# ExtPlateSheet1.net
KiCad netlist of a schematic drawn in Altium Designer
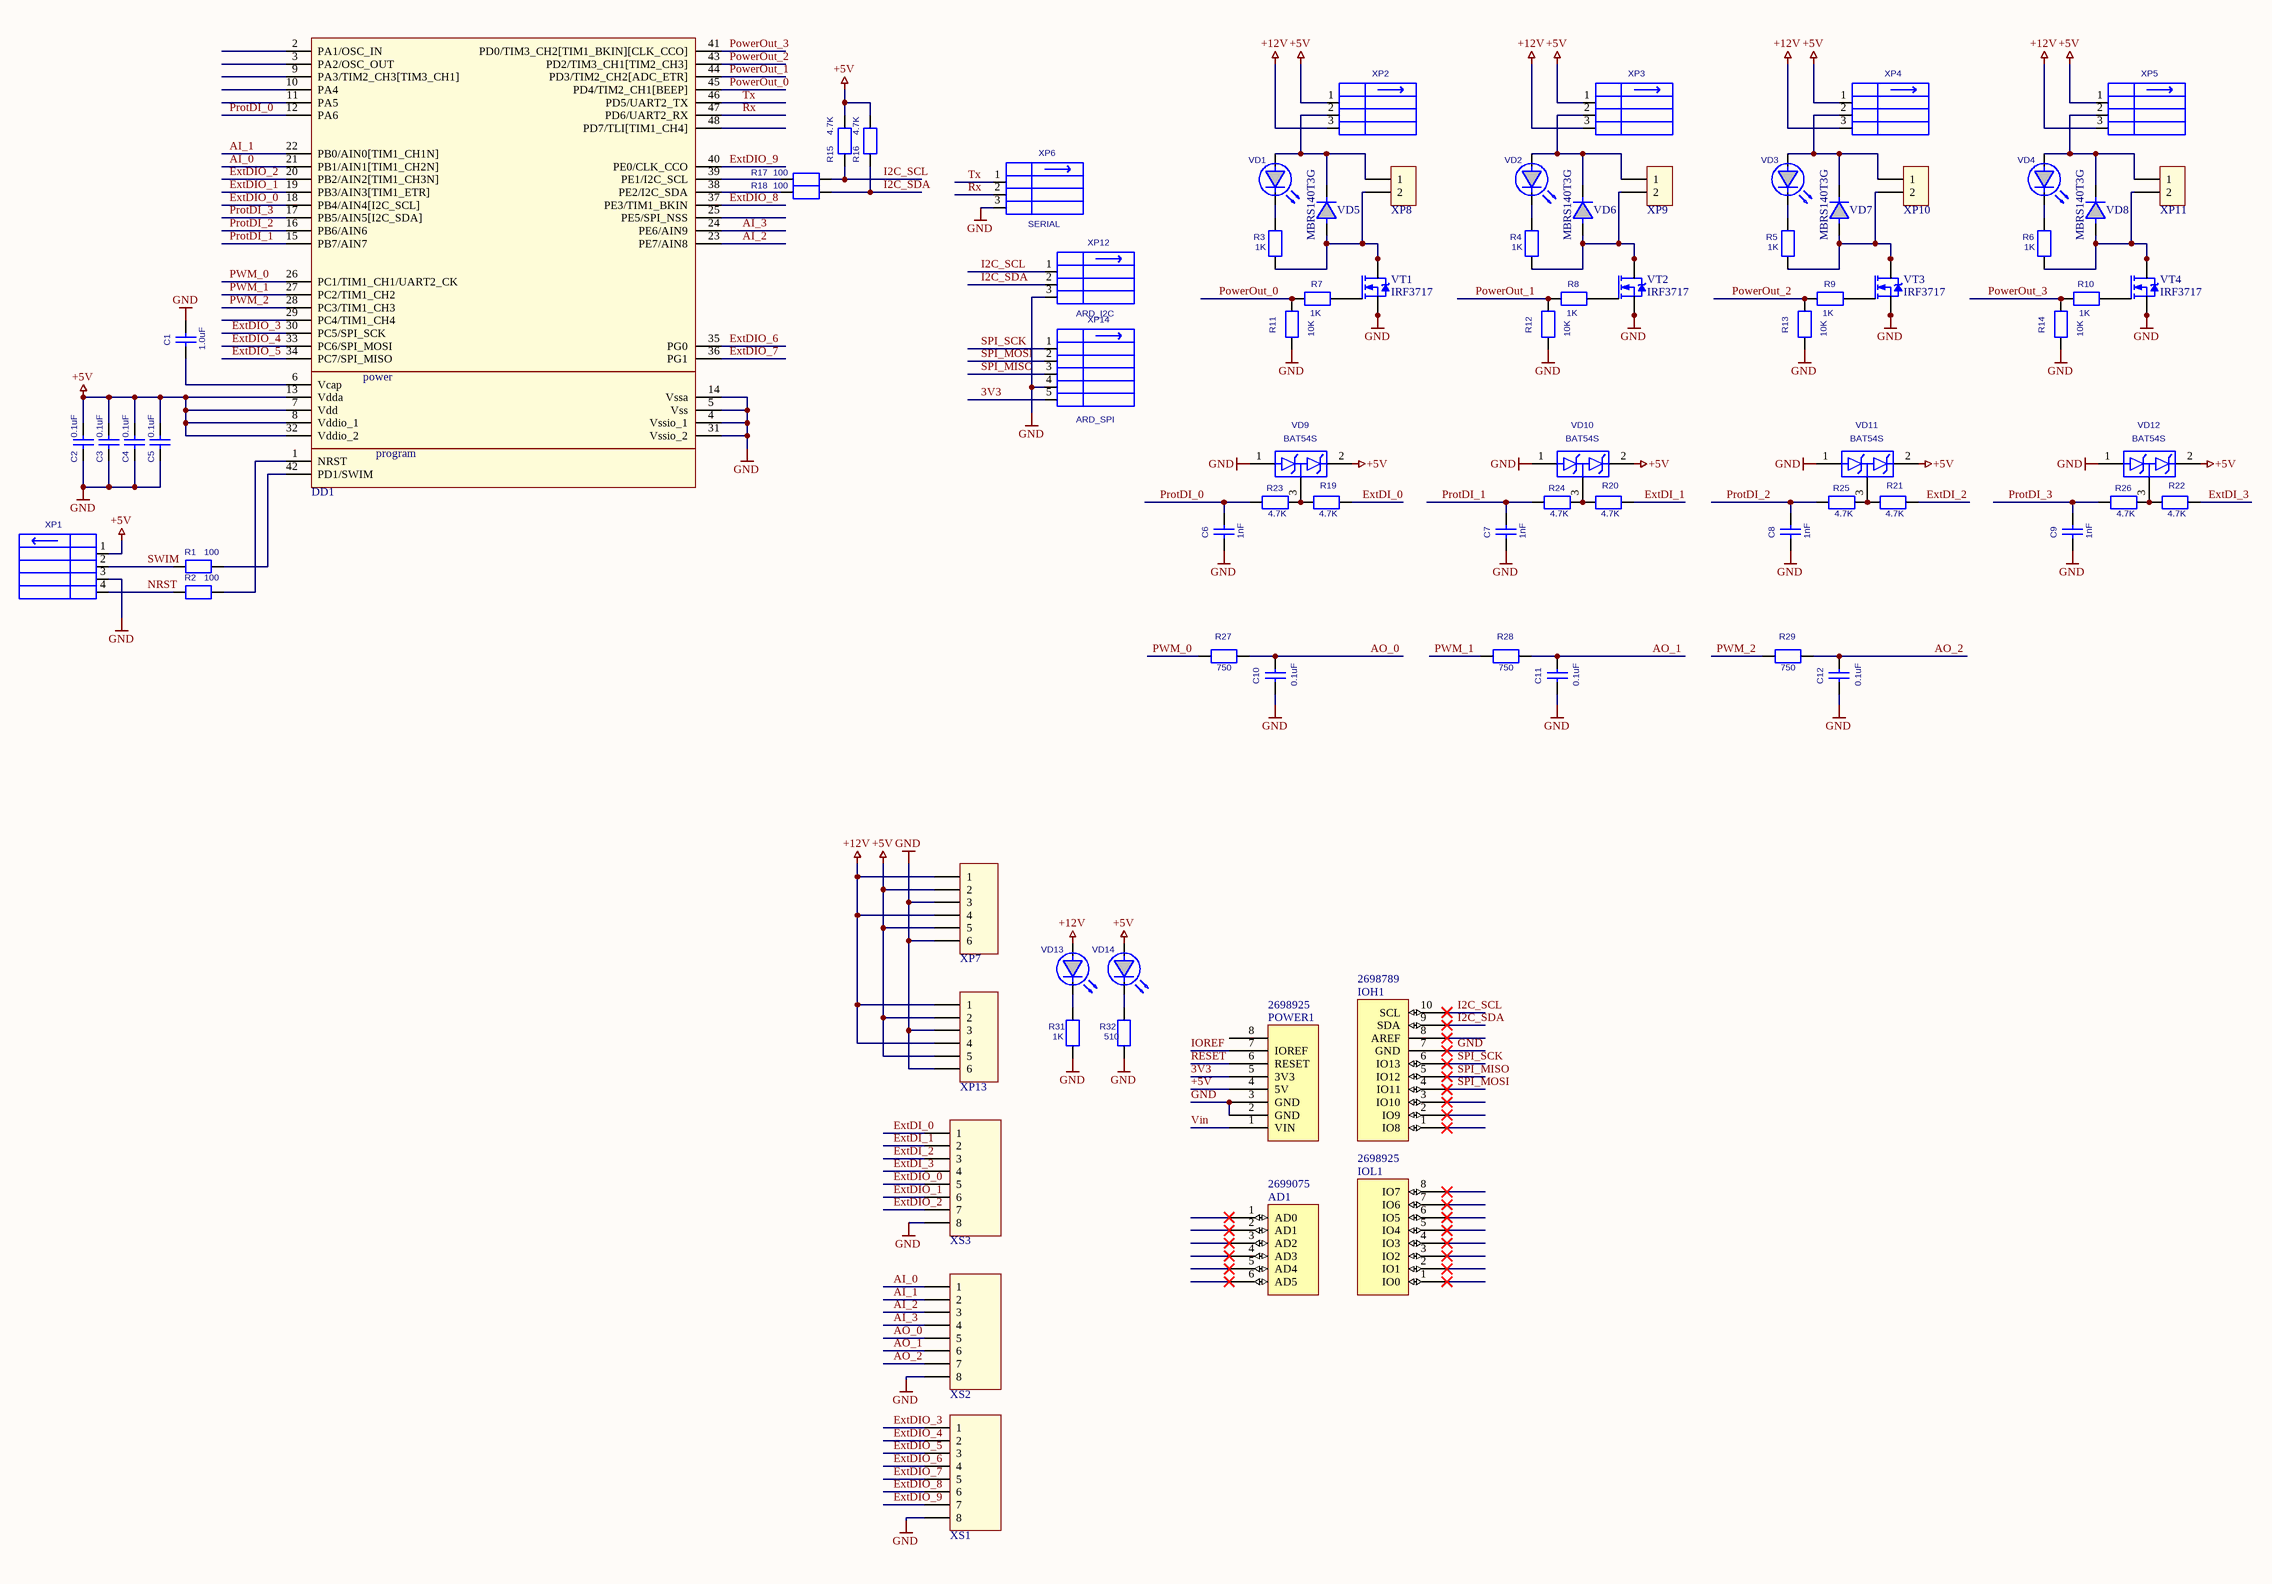
[diagram p0: ExtPlateSheet1.SchDoc]

(export (version "E")
  (design (tool "Eeschema 10.0.6"))
  (components
    (comp (ref "AD1")
      (value "AD")
      (footprint "Altium-CONN:PLS6")
      (fields (field (name "SUPPLIER PART NUMBER 4") "2699075"))
      (libsource (lib "Header") (part "AD"))
    )
    (comp (ref "C1")
      (value "1.0uF")
      (footprint "C-1608[0603]")
      (description "C-0603")
      (libsource (lib "Altium-RC") (part "C-0603"))
    )
    (comp (ref "C2")
      (value "0.1uF")
      (footprint "C-1608[0603]")
      (description "C-0603")
      (libsource (lib "Altium-RC") (part "C-0603"))
    )
    (comp (ref "C3")
      (value "0.1uF")
      (footprint "C-1608[0603]")
      (description "C-0603")
      (libsource (lib "Altium-RC") (part "C-0603"))
    )
    (comp (ref "C4")
      (value "0.1uF")
      (footprint "C-1608[0603]")
      (description "C-0603")
      (libsource (lib "Altium-RC") (part "C-0603"))
    )
    (comp (ref "C5")
      (value "0.1uF")
      (footprint "C-1608[0603]")
      (description "C-0603")
      (libsource (lib "Altium-RC") (part "C-0603"))
    )
    (comp (ref "C6")
      (value "1nF")
      (footprint "C-1608[0603]")
      (description "C-0603")
      (libsource (lib "Altium-RC") (part "C-0603"))
    )
    (comp (ref "C7")
      (value "1nF")
      (footprint "C-1608[0603]")
      (description "C-0603")
      (libsource (lib "Altium-RC") (part "C-0603"))
    )
    (comp (ref "C8")
      (value "1nF")
      (footprint "C-1608[0603]")
      (description "C-0603")
      (libsource (lib "Altium-RC") (part "C-0603"))
    )
    (comp (ref "C9")
      (value "1nF")
      (footprint "C-1608[0603]")
      (description "C-0603")
      (libsource (lib "Altium-RC") (part "C-0603"))
    )
    (comp (ref "C10")
      (value "0.1uF")
      (footprint "C-1608[0603]")
      (description "C-0603")
      (libsource (lib "Altium-RC") (part "C-0603"))
    )
    (comp (ref "C11")
      (value "0.1uF")
      (footprint "C-1608[0603]")
      (description "C-0603")
      (libsource (lib "Altium-RC") (part "C-0603"))
    )
    (comp (ref "C12")
      (value "0.1uF")
      (footprint "C-1608[0603]")
      (description "C-0603")
      (libsource (lib "Altium-RC") (part "C-0603"))
    )
    (comp (ref "DD1")
      (value "STM8S105Cx")
      (footprint "LQFP48_N")
      (description "Access line, 16 MHz STM8S 8-bit MCU")
      (libsource (lib "Schlib1") (part "STM8S105C"))
    )
    (comp (ref "IOH1")
      (value "IOH")
      (footprint "Altium-CONN:PLS10")
      (fields (field (name "SUPPLIER PART NUMBER 3") "2698789"))
      (libsource (lib "Header") (part "IOH"))
    )
    (comp (ref "IOL1")
      (value "IOL")
      (footprint "PLS8")
      (fields (field (name "SUPPLIER PART NUMBER 4") "2698925"))
      (libsource (lib "Header") (part "IOL"))
    )
    (comp (ref "POWER1")
      (value "POWER_UNO")
      (footprint "PLS8")
      (fields (field (name "SUPPLIER PART NUMBER 4") "2698925"))
      (libsource (lib "Header") (part "POWER_UNO"))
    )
    (comp (ref "R1")
      (value "100")
      (footprint "R-1608[0603]")
      (description "R-0603")
      (libsource (lib "Altium-RC") (part "R-0603"))
    )
    (comp (ref "R2")
      (value "100")
      (footprint "R-1608[0603]")
      (description "R-0603")
      (libsource (lib "Altium-RC") (part "R-0603"))
    )
    (comp (ref "R3")
      (value "1K")
      (footprint "R-1608[0603]")
      (description "R-0603")
      (libsource (lib "Altium-RC") (part "R-0603"))
    )
    (comp (ref "R4")
      (value "1K")
      (footprint "R-1608[0603]")
      (description "R-0603")
      (libsource (lib "Altium-RC") (part "R-0603"))
    )
    (comp (ref "R5")
      (value "1K")
      (footprint "R-1608[0603]")
      (description "R-0603")
      (libsource (lib "Altium-RC") (part "R-0603"))
    )
    (comp (ref "R6")
      (value "1K")
      (footprint "R-1608[0603]")
      (description "R-0603")
      (libsource (lib "Altium-RC") (part "R-0603"))
    )
    (comp (ref "R7")
      (value "1K")
      (footprint "R-1608[0603]")
      (description "R-0603")
      (libsource (lib "Altium-RC") (part "R-0603"))
    )
    (comp (ref "R8")
      (value "1K")
      (footprint "R-1608[0603]")
      (description "R-0603")
      (libsource (lib "Altium-RC") (part "R-0603"))
    )
    (comp (ref "R9")
      (value "1K")
      (footprint "R-1608[0603]")
      (description "R-0603")
      (libsource (lib "Altium-RC") (part "R-0603"))
    )
    (comp (ref "R10")
      (value "1K")
      (footprint "R-1608[0603]")
      (description "R-0603")
      (libsource (lib "Altium-RC") (part "R-0603"))
    )
    (comp (ref "R11")
      (value "10K")
      (footprint "R-1608[0603]")
      (description "R-0603")
      (libsource (lib "Altium-RC") (part "R-0603"))
    )
    (comp (ref "R12")
      (value "10K")
      (footprint "R-1608[0603]")
      (description "R-0603")
      (libsource (lib "Altium-RC") (part "R-0603"))
    )
    (comp (ref "R13")
      (value "10K")
      (footprint "R-1608[0603]")
      (description "R-0603")
      (libsource (lib "Altium-RC") (part "R-0603"))
    )
    (comp (ref "R14")
      (value "10K")
      (footprint "R-1608[0603]")
      (description "R-0603")
      (libsource (lib "Altium-RC") (part "R-0603"))
    )
    (comp (ref "R15")
      (value "4.7K")
      (footprint "R-1608[0603]")
      (description "R-0603")
      (libsource (lib "Altium-RC") (part "R-0603"))
    )
    (comp (ref "R16")
      (value "4.7K")
      (footprint "R-1608[0603]")
      (description "R-0603")
      (libsource (lib "Altium-RC") (part "R-0603"))
    )
    (comp (ref "R17")
      (value "100")
      (footprint "R-1608[0603]")
      (description "R-0603")
      (libsource (lib "Altium-RC") (part "R-0603"))
    )
    (comp (ref "R18")
      (value "100")
      (footprint "R-1608[0603]")
      (description "R-0603")
      (libsource (lib "Altium-RC") (part "R-0603"))
    )
    (comp (ref "R19")
      (value "4.7K")
      (footprint "R-1608[0603]")
      (description "R-0603")
      (libsource (lib "Altium-RC") (part "R-0603"))
    )
    (comp (ref "R20")
      (value "4.7K")
      (footprint "R-1608[0603]")
      (description "R-0603")
      (libsource (lib "Altium-RC") (part "R-0603"))
    )
    (comp (ref "R21")
      (value "4.7K")
      (footprint "R-1608[0603]")
      (description "R-0603")
      (libsource (lib "Altium-RC") (part "R-0603"))
    )
    (comp (ref "R22")
      (value "4.7K")
      (footprint "R-1608[0603]")
      (description "R-0603")
      (libsource (lib "Altium-RC") (part "R-0603"))
    )
    (comp (ref "R23")
      (value "4.7K")
      (footprint "R-1608[0603]")
      (description "R-0603")
      (libsource (lib "Altium-RC") (part "R-0603"))
    )
    (comp (ref "R24")
      (value "4.7K")
      (footprint "R-1608[0603]")
      (description "R-0603")
      (libsource (lib "Altium-RC") (part "R-0603"))
    )
    (comp (ref "R25")
      (value "4.7K")
      (footprint "R-1608[0603]")
      (description "R-0603")
      (libsource (lib "Altium-RC") (part "R-0603"))
    )
    (comp (ref "R26")
      (value "4.7K")
      (footprint "R-1608[0603]")
      (description "R-0603")
      (libsource (lib "Altium-RC") (part "R-0603"))
    )
    (comp (ref "R27")
      (value "750")
      (footprint "R-1608[0603]")
      (description "R-0603")
      (libsource (lib "Altium-RC") (part "R-0603"))
    )
    (comp (ref "R28")
      (value "750")
      (footprint "R-1608[0603]")
      (description "R-0603")
      (libsource (lib "Altium-RC") (part "R-0603"))
    )
    (comp (ref "R29")
      (value "750")
      (footprint "R-1608[0603]")
      (description "R-0603")
      (libsource (lib "Altium-RC") (part "R-0603"))
    )
    (comp (ref "R31")
      (value "1K")
      (footprint "R-1608[0603]")
      (description "R-0603")
      (libsource (lib "Altium-RC") (part "R-0603"))
    )
    (comp (ref "R32")
      (value "510")
      (footprint "R-1608[0603]")
      (description "R-0603")
      (libsource (lib "Altium-RC") (part "R-0603"))
    )
    (comp (ref "VD1")
      (value "KB170G")
      (footprint "LED-2012[0805]")
      (description "Green Led 0805")
      (libsource (lib "Altium-OPTO") (part "KB170G"))
    )
    (comp (ref "VD2")
      (value "KB170G")
      (footprint "LED-2012[0805]")
      (description "Green Led 0805")
      (libsource (lib "Altium-OPTO") (part "KB170G"))
    )
    (comp (ref "VD3")
      (value "KB170G")
      (footprint "LED-2012[0805]")
      (description "Green Led 0805")
      (libsource (lib "Altium-OPTO") (part "KB170G"))
    )
    (comp (ref "VD4")
      (value "KB170G")
      (footprint "LED-2012[0805]")
      (description "Green Led 0805")
      (libsource (lib "Altium-OPTO") (part "KB170G"))
    )
    (comp (ref "VD5")
      (value "MBRS140T3G")
      (footprint "SMB")
      (description "Surface Mount Schottky Power Rectifier")
      (libsource (lib "Altium-RECT") (part "MBRS140T3G"))
    )
    (comp (ref "VD6")
      (value "MBRS140T3G")
      (footprint "SMB")
      (description "Surface Mount Schottky Power Rectifier")
      (libsource (lib "Altium-RECT") (part "MBRS140T3G"))
    )
    (comp (ref "VD7")
      (value "MBRS140T3G")
      (footprint "SMB")
      (description "Surface Mount Schottky Power Rectifier")
      (libsource (lib "Altium-RECT") (part "MBRS140T3G"))
    )
    (comp (ref "VD8")
      (value "MBRS140T3G")
      (footprint "SMB")
      (description "Surface Mount Schottky Power Rectifier")
      (libsource (lib "Altium-RECT") (part "MBRS140T3G"))
    )
    (comp (ref "VD9")
      (value "BAT54S")
      (footprint "SOT-23")
      (description "Schottky barrier (double) diodes")
      (libsource (lib "Altium-RECT") (part "BAT54S"))
    )
    (comp (ref "VD10")
      (value "BAT54S")
      (footprint "SOT-23")
      (description "Schottky barrier (double) diodes")
      (libsource (lib "Altium-RECT") (part "BAT54S"))
    )
    (comp (ref "VD11")
      (value "BAT54S")
      (footprint "SOT-23")
      (description "Schottky barrier (double) diodes")
      (libsource (lib "Altium-RECT") (part "BAT54S"))
    )
    (comp (ref "VD12")
      (value "BAT54S")
      (footprint "SOT-23")
      (description "Schottky barrier (double) diodes")
      (libsource (lib "Altium-RECT") (part "BAT54S"))
    )
    (comp (ref "VD13")
      (value "KB170G")
      (footprint "LED-2012[0805]")
      (description "Green Led 0805")
      (libsource (lib "Altium-OPTO") (part "KB170G"))
    )
    (comp (ref "VD14")
      (value "KB170G")
      (footprint "LED-2012[0805]")
      (description "Green Led 0805")
      (libsource (lib "Altium-OPTO") (part "KB170G"))
    )
    (comp (ref "VT1") (value "IRF3717") (footprint "SO8") (libsource (lib "Altium-RECT") (part "IRF3717")))
    (comp (ref "VT2") (value "IRF3717") (footprint "SO8") (libsource (lib "Altium-RECT") (part "IRF3717")))
    (comp (ref "VT3") (value "IRF3717") (footprint "SO8") (libsource (lib "Altium-RECT") (part "IRF3717")))
    (comp (ref "VT4") (value "IRF3717") (footprint "SO8") (libsource (lib "Altium-RECT") (part "IRF3717")))
    (comp (ref "XP1") (value "PLS-4") (footprint "PLS4") (libsource (lib "Altium-CONN") (part "PLS-4")))
    (comp (ref "XP2") (value "PLS-3") (footprint "PLS3") (libsource (lib "Altium-CONN") (part "PLS-3")))
    (comp (ref "XP3") (value "PLS-3") (footprint "PLS3") (libsource (lib "Altium-CONN") (part "PLS-3")))
    (comp (ref "XP4") (value "PLS-3") (footprint "PLS3") (libsource (lib "Altium-CONN") (part "PLS-3")))
    (comp (ref "XP5") (value "PLS-3") (footprint "PLS3") (libsource (lib "Altium-CONN") (part "PLS-3")))
    (comp (ref "XP6")
      (value "SERIAL")
      (footprint "PLS3")
      (description "PLS-3")
      (libsource (lib "Altium-CONN") (part "PLS-3"))
    )
    (comp (ref "XP7")
      (value "MF-6M")
      (footprint "MF-6M")
      (description "Mini-Fit 6 pin Connector on board.")
      (libsource (lib "Schlib1") (part "MF-6M"))
    )
    (comp (ref "XP8")
      (value "2EDGR-5.08")
      (footprint "2EDGR-5.08")
      (libsource (lib "Schlib1") (part "2EDGR-5.08"))
    )
    (comp (ref "XP9")
      (value "2EDGR-5.08")
      (footprint "2EDGR-5.08")
      (libsource (lib "Schlib1") (part "2EDGR-5.08"))
    )
    (comp (ref "XP10")
      (value "2EDGR-5.08")
      (footprint "2EDGR-5.08")
      (libsource (lib "Schlib1") (part "2EDGR-5.08"))
    )
    (comp (ref "XP11")
      (value "2EDGR-5.08")
      (footprint "2EDGR-5.08")
      (libsource (lib "Schlib1") (part "2EDGR-5.08"))
    )
    (comp (ref "XP12")
      (value "ARD_I2C")
      (footprint "PLS3")
      (description "PLS-3")
      (libsource (lib "Altium-CONN") (part "PLS-3"))
    )
    (comp (ref "XP13")
      (value "MF-6M")
      (footprint "MF-6M")
      (description "Mini-Fit 6 pin Connector on board.")
      (libsource (lib "Schlib1") (part "MF-6M"))
    )
    (comp (ref "XP14")
      (value "ARD_SPI")
      (footprint "PLS5")
      (description "PLS-5")
      (libsource (lib "Altium-CONN") (part "PLS-5"))
    )
    (comp (ref "XS1")
      (value "5555164-1")
      (footprint "RJ45 8pin")
      (description "PCB Mounted Jacks - Single Port, Multi-port and Stacked")
      (libsource (lib "Schlib1") (part "5555164-1"))
    )
    (comp (ref "XS2")
      (value "5555164-1")
      (footprint "RJ45 8pin")
      (description "PCB Mounted Jacks - Single Port, Multi-port and Stacked")
      (libsource (lib "Schlib1") (part "5555164-1"))
    )
    (comp (ref "XS3")
      (value "5555164-1")
      (footprint "RJ45 8pin")
      (description "PCB Mounted Jacks - Single Port, Multi-port and Stacked")
      (libsource (lib "Schlib1") (part "5555164-1"))
    )
  )
  (nets
    (net (code "1") (name "+5V") (class "Default")
      (node (ref "C2") (pin "1") (pintype "passive"))
      (node (ref "C3") (pin "1") (pintype "passive"))
      (node (ref "C4") (pin "1") (pintype "passive"))
      (node (ref "C5") (pin "1") (pintype "passive"))
      (node (ref "DD1") (pin "13") (pinfunction "Vdda_13") (pintype "passive"))
      (node (ref "DD1") (pin "32") (pinfunction "Vddio_2_32") (pintype "passive"))
      (node (ref "DD1") (pin "7") (pinfunction "Vdd_7") (pintype "passive"))
      (node (ref "DD1") (pin "8") (pinfunction "Vddio_1_8") (pintype "passive"))
      (node (ref "POWER1") (pin "4") (pinfunction "5V_4") (pintype "power_in"))
      (node (ref "R15") (pin "2") (pinfunction "2_2") (pintype "passive"))
      (node (ref "R16") (pin "2") (pinfunction "2_2") (pintype "passive"))
      (node (ref "VD10") (pin "2") (pinfunction "c_2") (pintype "passive"))
      (node (ref "VD11") (pin "2") (pinfunction "c_2") (pintype "passive"))
      (node (ref "VD12") (pin "2") (pinfunction "c_2") (pintype "passive"))
      (node (ref "VD14") (pin "2") (pinfunction "A_2") (pintype "passive"))
      (node (ref "VD9") (pin "2") (pinfunction "c_2") (pintype "passive"))
      (node (ref "XP1") (pin "1") (pintype "passive"))
      (node (ref "XP13") (pin "2") (pinfunction "2_2") (pintype "passive"))
      (node (ref "XP13") (pin "5") (pinfunction "5_5") (pintype "passive"))
      (node (ref "XP2") (pin "1") (pintype "passive"))
      (node (ref "XP3") (pin "1") (pintype "passive"))
      (node (ref "XP4") (pin "1") (pintype "passive"))
      (node (ref "XP5") (pin "1") (pintype "passive"))
      (node (ref "XP7") (pin "2") (pinfunction "2_2") (pintype "passive"))
      (node (ref "XP7") (pin "5") (pinfunction "5_5") (pintype "passive"))
    )
    (net (code "2") (name "+12V") (class "Default")
      (node (ref "VD13") (pin "2") (pinfunction "A_2") (pintype "passive"))
      (node (ref "XP13") (pin "1") (pinfunction "1_1") (pintype "passive"))
      (node (ref "XP13") (pin "4") (pinfunction "4_4") (pintype "passive"))
      (node (ref "XP2") (pin "3") (pintype "passive"))
      (node (ref "XP3") (pin "3") (pintype "passive"))
      (node (ref "XP4") (pin "3") (pintype "passive"))
      (node (ref "XP5") (pin "3") (pintype "passive"))
      (node (ref "XP7") (pin "1") (pinfunction "1_1") (pintype "passive"))
      (node (ref "XP7") (pin "4") (pinfunction "4_4") (pintype "passive"))
    )
    (net (code "3") (name "/3V3") (class "Default")
      (node (ref "POWER1") (pin "5") (pinfunction "3V3_5") (pintype "power_in"))
      (node (ref "XP14") (pin "5") (pintype "passive"))
    )
    (net (code "5") (name "/AI_0") (class "Default")
      (node (ref "DD1") (pin "21") (pinfunction "PB1/AIN1[TIM1_CH2N]_21") (pintype "passive"))
      (node (ref "XS2") (pin "1") (pinfunction "1_1") (pintype "passive"))
    )
    (net (code "6") (name "/AI_1") (class "Default")
      (node (ref "DD1") (pin "22") (pinfunction "PB0/AIN0[TIM1_CH1N]_22") (pintype "passive"))
      (node (ref "XS2") (pin "2") (pinfunction "2_2") (pintype "passive"))
    )
    (net (code "7") (name "/AI_2") (class "Default")
      (node (ref "DD1") (pin "23") (pinfunction "PE7/AIN8_23") (pintype "passive"))
      (node (ref "XS2") (pin "3") (pinfunction "3_3") (pintype "passive"))
    )
    (net (code "8") (name "/AI_3") (class "Default")
      (node (ref "DD1") (pin "24") (pinfunction "PE6/AIN9_24") (pintype "passive"))
      (node (ref "XS2") (pin "4") (pinfunction "4_4") (pintype "passive"))
    )
    (net (code "9") (name "/AO_0") (class "Default")
      (node (ref "C10") (pin "1") (pintype "passive"))
      (node (ref "R27") (pin "2") (pinfunction "2_2") (pintype "passive"))
      (node (ref "XS2") (pin "5") (pinfunction "5_5") (pintype "passive"))
    )
    (net (code "10") (name "/AO_1") (class "Default")
      (node (ref "C11") (pin "1") (pintype "passive"))
      (node (ref "R28") (pin "2") (pinfunction "2_2") (pintype "passive"))
      (node (ref "XS2") (pin "6") (pinfunction "6_6") (pintype "passive"))
    )
    (net (code "11") (name "/AO_2") (class "Default")
      (node (ref "C12") (pin "1") (pintype "passive"))
      (node (ref "R29") (pin "2") (pinfunction "2_2") (pintype "passive"))
      (node (ref "XS2") (pin "7") (pinfunction "7_7") (pintype "passive"))
    )
    (net (code "12") (name "/ExtDIO_0") (class "Default")
      (node (ref "DD1") (pin "18") (pinfunction "PB4/AIN4[I2C_SCL]_18") (pintype "passive"))
      (node (ref "XS3") (pin "5") (pinfunction "5_5") (pintype "passive"))
    )
    (net (code "13") (name "/ExtDIO_1") (class "Default")
      (node (ref "DD1") (pin "19") (pinfunction "PB3/AIN3[TIM1_ETR]_19") (pintype "passive"))
      (node (ref "XS3") (pin "6") (pinfunction "6_6") (pintype "passive"))
    )
    (net (code "14") (name "/ExtDIO_2") (class "Default")
      (node (ref "DD1") (pin "20") (pinfunction "PB2/AIN2[TIM1_CH3N]_20") (pintype "passive"))
      (node (ref "XS3") (pin "7") (pinfunction "7_7") (pintype "passive"))
    )
    (net (code "15") (name "/ExtDIO_3") (class "Default")
      (node (ref "DD1") (pin "30") (pinfunction "PC5/SPI_SCK_30") (pintype "passive"))
      (node (ref "XS1") (pin "1") (pinfunction "1_1") (pintype "passive"))
    )
    (net (code "16") (name "/ExtDIO_4") (class "Default")
      (node (ref "DD1") (pin "33") (pinfunction "PC6/SPI_MOSI_33") (pintype "passive"))
      (node (ref "XS1") (pin "2") (pinfunction "2_2") (pintype "passive"))
    )
    (net (code "17") (name "/ExtDIO_5") (class "Default")
      (node (ref "DD1") (pin "34") (pinfunction "PC7/SPI_MISO_34") (pintype "passive"))
      (node (ref "XS1") (pin "3") (pinfunction "3_3") (pintype "passive"))
    )
    (net (code "18") (name "/ExtDIO_6") (class "Default")
      (node (ref "DD1") (pin "35") (pinfunction "PG0_35") (pintype "passive"))
      (node (ref "XS1") (pin "4") (pinfunction "4_4") (pintype "passive"))
    )
    (net (code "19") (name "/ExtDIO_7") (class "Default")
      (node (ref "DD1") (pin "36") (pinfunction "PG1_36") (pintype "passive"))
      (node (ref "XS1") (pin "5") (pinfunction "5_5") (pintype "passive"))
    )
    (net (code "20") (name "/ExtDIO_8") (class "Default")
      (node (ref "DD1") (pin "37") (pinfunction "PE3/TIM1_BKIN_37") (pintype "passive"))
      (node (ref "XS1") (pin "6") (pinfunction "6_6") (pintype "passive"))
    )
    (net (code "21") (name "/ExtDIO_9") (class "Default")
      (node (ref "DD1") (pin "40") (pinfunction "PE0/CLK_CCO_40") (pintype "passive"))
      (node (ref "XS1") (pin "7") (pinfunction "7_7") (pintype "passive"))
    )
    (net (code "22") (name "/ExtDI_0") (class "Default")
      (node (ref "R19") (pin "2") (pinfunction "2_2") (pintype "passive"))
      (node (ref "XS3") (pin "1") (pinfunction "1_1") (pintype "passive"))
    )
    (net (code "23") (name "/ExtDI_1") (class "Default")
      (node (ref "R20") (pin "2") (pinfunction "2_2") (pintype "passive"))
      (node (ref "XS3") (pin "2") (pinfunction "2_2") (pintype "passive"))
    )
    (net (code "24") (name "/ExtDI_2") (class "Default")
      (node (ref "R21") (pin "2") (pinfunction "2_2") (pintype "passive"))
      (node (ref "XS3") (pin "3") (pinfunction "3_3") (pintype "passive"))
    )
    (net (code "25") (name "/ExtDI_3") (class "Default")
      (node (ref "R22") (pin "2") (pinfunction "2_2") (pintype "passive"))
      (node (ref "XS3") (pin "4") (pinfunction "4_4") (pintype "passive"))
    )
    (net (code "26") (name "/I2C_SCL") (class "Default")
      (node (ref "IOH1") (pin "10") (pinfunction "SCL_10") (pintype "bidirectional"))
      (node (ref "R15") (pin "1") (pinfunction "1_1") (pintype "passive"))
      (node (ref "R17") (pin "2") (pinfunction "2_2") (pintype "passive"))
      (node (ref "XP12") (pin "1") (pintype "passive"))
    )
    (net (code "27") (name "/I2C_SDA") (class "Default")
      (node (ref "IOH1") (pin "9") (pinfunction "SDA_9") (pintype "bidirectional"))
      (node (ref "R16") (pin "1") (pinfunction "1_1") (pintype "passive"))
      (node (ref "R18") (pin "2") (pinfunction "2_2") (pintype "passive"))
      (node (ref "XP12") (pin "2") (pintype "passive"))
    )
    (net (code "28") (name "/IOREF") (class "Default")
      (node (ref "POWER1") (pin "7") (pinfunction "IOREF_7") (pintype "power_in"))
    )
    (net (code "29") (name "/NRST") (class "Default")
      (node (ref "R2") (pin "1") (pinfunction "1_1") (pintype "passive"))
      (node (ref "XP1") (pin "4") (pintype "passive"))
    )
    (net (code "30") (name "/PWM_0") (class "Default")
      (node (ref "DD1") (pin "26") (pinfunction "PC1/TIM1_CH1/UART2_CK_26") (pintype "passive"))
      (node (ref "R27") (pin "1") (pinfunction "1_1") (pintype "passive"))
    )
    (net (code "31") (name "/PWM_1") (class "Default")
      (node (ref "DD1") (pin "27") (pinfunction "PC2/TIM1_CH2_27") (pintype "passive"))
      (node (ref "R28") (pin "1") (pinfunction "1_1") (pintype "passive"))
    )
    (net (code "32") (name "/PWM_2") (class "Default")
      (node (ref "DD1") (pin "28") (pinfunction "PC3/TIM1_CH3_28") (pintype "passive"))
      (node (ref "R29") (pin "1") (pinfunction "1_1") (pintype "passive"))
    )
    (net (code "33") (name "/PowerOut_0") (class "Default")
      (node (ref "DD1") (pin "45") (pinfunction "PD4/TIM2_CH1[BEEP]_45") (pintype "passive"))
      (node (ref "R11") (pin "2") (pinfunction "2_2") (pintype "passive"))
      (node (ref "R7") (pin "2") (pinfunction "2_2") (pintype "passive"))
    )
    (net (code "34") (name "/PowerOut_1") (class "Default")
      (node (ref "DD1") (pin "44") (pinfunction "PD3/TIM2_CH2[ADC_ETR]_44") (pintype "passive"))
      (node (ref "R12") (pin "2") (pinfunction "2_2") (pintype "passive"))
      (node (ref "R8") (pin "2") (pinfunction "2_2") (pintype "passive"))
    )
    (net (code "35") (name "/PowerOut_2") (class "Default")
      (node (ref "DD1") (pin "43") (pinfunction "PD2/TIM3_CH1[TIM2_CH3]_43") (pintype "passive"))
      (node (ref "R13") (pin "2") (pinfunction "2_2") (pintype "passive"))
      (node (ref "R9") (pin "2") (pinfunction "2_2") (pintype "passive"))
    )
    (net (code "36") (name "/PowerOut_3") (class "Default")
      (node (ref "DD1") (pin "41") (pinfunction "PD0/TIM3_CH2[TIM1_BKIN][CLK_CCO]_41") (pintype "passive"))
      (node (ref "R10") (pin "2") (pinfunction "2_2") (pintype "passive"))
      (node (ref "R14") (pin "2") (pinfunction "2_2") (pintype "passive"))
    )
    (net (code "37") (name "/ProtDI_0") (class "Default")
      (node (ref "C6") (pin "1") (pintype "passive"))
      (node (ref "DD1") (pin "12") (pinfunction "PA6_12") (pintype "passive"))
      (node (ref "R23") (pin "1") (pinfunction "1_1") (pintype "passive"))
    )
    (net (code "38") (name "/ProtDI_1") (class "Default")
      (node (ref "C7") (pin "1") (pintype "passive"))
      (node (ref "DD1") (pin "15") (pinfunction "PB7/AIN7_15") (pintype "passive"))
      (node (ref "R24") (pin "1") (pinfunction "1_1") (pintype "passive"))
    )
    (net (code "39") (name "/ProtDI_2") (class "Default")
      (node (ref "C8") (pin "1") (pintype "passive"))
      (node (ref "DD1") (pin "16") (pinfunction "PB6/AIN6_16") (pintype "passive"))
      (node (ref "R25") (pin "1") (pinfunction "1_1") (pintype "passive"))
    )
    (net (code "40") (name "/ProtDI_3") (class "Default")
      (node (ref "C9") (pin "1") (pintype "passive"))
      (node (ref "DD1") (pin "17") (pinfunction "PB5/AIN5[I2C_SDA]_17") (pintype "passive"))
      (node (ref "R26") (pin "1") (pinfunction "1_1") (pintype "passive"))
    )
    (net (code "41") (name "/RESET") (class "Default")
      (node (ref "POWER1") (pin "6") (pinfunction "RESET_6") (pintype "passive"))
    )
    (net (code "42") (name "/Rx") (class "Default")
      (node (ref "DD1") (pin "47") (pinfunction "PD6/UART2_RX_47") (pintype "passive"))
      (node (ref "XP6") (pin "2") (pintype "passive"))
    )
    (net (code "43") (name "/SPI_MISO") (class "Default")
      (node (ref "IOH1") (pin "5") (pinfunction "IO12_5") (pintype "bidirectional"))
      (node (ref "XP14") (pin "3") (pintype "passive"))
    )
    (net (code "44") (name "/SPI_MOSI") (class "Default")
      (node (ref "IOH1") (pin "4") (pinfunction "IO11_4") (pintype "bidirectional"))
      (node (ref "XP14") (pin "2") (pintype "passive"))
    )
    (net (code "45") (name "/SPI_SCK") (class "Default")
      (node (ref "IOH1") (pin "6") (pinfunction "IO13_6") (pintype "bidirectional"))
      (node (ref "XP14") (pin "1") (pintype "passive"))
    )
    (net (code "46") (name "/SWIM") (class "Default")
      (node (ref "R1") (pin "1") (pinfunction "1_1") (pintype "passive"))
      (node (ref "XP1") (pin "2") (pintype "passive"))
    )
    (net (code "47") (name "/Tx") (class "Default")
      (node (ref "DD1") (pin "46") (pinfunction "PD5/UART2_TX_46") (pintype "passive"))
      (node (ref "XP6") (pin "1") (pintype "passive"))
    )
    (net (code "48") (name "/Vin") (class "Default")
      (node (ref "POWER1") (pin "1") (pinfunction "VIN_1") (pintype "power_in"))
    )
    (net (code "49") (name "GND") (class "Default")
      (node (ref "C1") (pin "1") (pintype "passive"))
      (node (ref "C10") (pin "2") (pintype "passive"))
      (node (ref "C11") (pin "2") (pintype "passive"))
      (node (ref "C12") (pin "2") (pintype "passive"))
      (node (ref "C2") (pin "2") (pintype "passive"))
      (node (ref "C3") (pin "2") (pintype "passive"))
      (node (ref "C4") (pin "2") (pintype "passive"))
      (node (ref "C5") (pin "2") (pintype "passive"))
      (node (ref "C6") (pin "2") (pintype "passive"))
      (node (ref "C7") (pin "2") (pintype "passive"))
      (node (ref "C8") (pin "2") (pintype "passive"))
      (node (ref "C9") (pin "2") (pintype "passive"))
      (node (ref "DD1") (pin "14") (pinfunction "Vssa_14") (pintype "passive"))
      (node (ref "DD1") (pin "31") (pinfunction "Vssio_2_31") (pintype "passive"))
      (node (ref "DD1") (pin "4") (pinfunction "Vssio_1_4") (pintype "passive"))
      (node (ref "DD1") (pin "5") (pinfunction "Vss_5") (pintype "passive"))
      (node (ref "IOH1") (pin "7") (pinfunction "GND_7") (pintype "power_in"))
      (node (ref "POWER1") (pin "2") (pinfunction "GND_2") (pintype "power_in"))
      (node (ref "POWER1") (pin "3") (pinfunction "GND_3") (pintype "power_in"))
      (node (ref "R11") (pin "1") (pinfunction "1_1") (pintype "passive"))
      (node (ref "R12") (pin "1") (pinfunction "1_1") (pintype "passive"))
      (node (ref "R13") (pin "1") (pinfunction "1_1") (pintype "passive"))
      (node (ref "R14") (pin "1") (pinfunction "1_1") (pintype "passive"))
      (node (ref "R31") (pin "2") (pinfunction "2_2") (pintype "passive"))
      (node (ref "R32") (pin "2") (pinfunction "2_2") (pintype "passive"))
      (node (ref "VD10") (pin "1") (pinfunction "a_1") (pintype "passive"))
      (node (ref "VD11") (pin "1") (pinfunction "a_1") (pintype "passive"))
      (node (ref "VD12") (pin "1") (pinfunction "a_1") (pintype "passive"))
      (node (ref "VD9") (pin "1") (pinfunction "a_1") (pintype "passive"))
      (node (ref "VT1") (pin "1") (pinfunction "1_1") (pintype "passive"))
      (node (ref "VT1") (pin "2") (pinfunction "2_2") (pintype "passive"))
      (node (ref "VT1") (pin "3") (pinfunction "3_3") (pintype "passive"))
      (node (ref "VT2") (pin "1") (pinfunction "1_1") (pintype "passive"))
      (node (ref "VT2") (pin "2") (pinfunction "2_2") (pintype "passive"))
      (node (ref "VT2") (pin "3") (pinfunction "3_3") (pintype "passive"))
      (node (ref "VT3") (pin "1") (pinfunction "1_1") (pintype "passive"))
      (node (ref "VT3") (pin "2") (pinfunction "2_2") (pintype "passive"))
      (node (ref "VT3") (pin "3") (pinfunction "3_3") (pintype "passive"))
      (node (ref "VT4") (pin "1") (pinfunction "1_1") (pintype "passive"))
      (node (ref "VT4") (pin "2") (pinfunction "2_2") (pintype "passive"))
      (node (ref "VT4") (pin "3") (pinfunction "3_3") (pintype "passive"))
      (node (ref "XP1") (pin "3") (pintype "passive"))
      (node (ref "XP12") (pin "3") (pintype "passive"))
      (node (ref "XP13") (pin "3") (pinfunction "3_3") (pintype "passive"))
      (node (ref "XP13") (pin "6") (pinfunction "6_6") (pintype "passive"))
      (node (ref "XP14") (pin "4") (pintype "passive"))
      (node (ref "XP6") (pin "3") (pintype "passive"))
      (node (ref "XP7") (pin "3") (pinfunction "3_3") (pintype "passive"))
      (node (ref "XP7") (pin "6") (pinfunction "6_6") (pintype "passive"))
      (node (ref "XS1") (pin "8") (pinfunction "8_8") (pintype "passive"))
      (node (ref "XS2") (pin "8") (pinfunction "8_8") (pintype "passive"))
      (node (ref "XS3") (pin "8") (pinfunction "8_8") (pintype "passive"))
    )
    (net (code "50") (name "Net-(DD1-NRST)") (class "Default")
      (node (ref "DD1") (pin "1") (pinfunction "NRST_1") (pintype "passive"))
      (node (ref "R2") (pin "2") (pinfunction "2_2") (pintype "passive"))
    )
    (net (code "51") (name "Net-(DD1-PD1{slash}SWIM)") (class "Default")
      (node (ref "DD1") (pin "42") (pinfunction "PD1/SWIM_42") (pintype "passive"))
      (node (ref "R1") (pin "2") (pinfunction "2_2") (pintype "passive"))
    )
    (net (code "52") (name "Net-(DD1-PE1{slash}I2C_SCL)") (class "Default")
      (node (ref "DD1") (pin "39") (pinfunction "PE1/I2C_SCL_39") (pintype "passive"))
      (node (ref "R17") (pin "1") (pinfunction "1_1") (pintype "passive"))
    )
    (net (code "53") (name "Net-(DD1-PE2{slash}I2C_SDA)") (class "Default")
      (node (ref "DD1") (pin "38") (pinfunction "PE2/I2C_SDA_38") (pintype "passive"))
      (node (ref "R18") (pin "1") (pinfunction "1_1") (pintype "passive"))
    )
    (net (code "54") (name "Net-(DD1-Vcap)") (class "Default")
      (node (ref "C1") (pin "2") (pintype "passive"))
      (node (ref "DD1") (pin "6") (pinfunction "Vcap_6") (pintype "passive"))
    )
    (net (code "55") (name "Net-(R7-Pad1)") (class "Default")
      (node (ref "R7") (pin "1") (pinfunction "1_1") (pintype "passive"))
      (node (ref "VT1") (pin "4") (pinfunction "4_4") (pintype "passive"))
    )
    (net (code "56") (name "Net-(R8-Pad1)") (class "Default")
      (node (ref "R8") (pin "1") (pinfunction "1_1") (pintype "passive"))
      (node (ref "VT2") (pin "4") (pinfunction "4_4") (pintype "passive"))
    )
    (net (code "57") (name "Net-(R9-Pad1)") (class "Default")
      (node (ref "R9") (pin "1") (pinfunction "1_1") (pintype "passive"))
      (node (ref "VT3") (pin "4") (pinfunction "4_4") (pintype "passive"))
    )
    (net (code "58") (name "Net-(R10-Pad1)") (class "Default")
      (node (ref "R10") (pin "1") (pinfunction "1_1") (pintype "passive"))
      (node (ref "VT4") (pin "4") (pinfunction "4_4") (pintype "passive"))
    )
    (net (code "59") (name "Net-(VD1-A)") (class "Default")
      (node (ref "VD1") (pin "2") (pinfunction "A_2") (pintype "passive"))
      (node (ref "VD5") (pin "1") (pinfunction "K_1") (pintype "passive"))
      (node (ref "XP2") (pin "2") (pintype "passive"))
      (node (ref "XP8") (pin "1") (pinfunction "1_1") (pintype "passive"))
    )
    (net (code "60") (name "Net-(VD1-K)") (class "Default")
      (node (ref "R3") (pin "1") (pinfunction "1_1") (pintype "passive"))
      (node (ref "VD1") (pin "1") (pinfunction "K_1") (pintype "passive"))
    )
    (net (code "61") (name "Net-(VD2-A)") (class "Default")
      (node (ref "VD2") (pin "2") (pinfunction "A_2") (pintype "passive"))
      (node (ref "VD6") (pin "1") (pinfunction "K_1") (pintype "passive"))
      (node (ref "XP3") (pin "2") (pintype "passive"))
      (node (ref "XP9") (pin "1") (pinfunction "1_1") (pintype "passive"))
    )
    (net (code "62") (name "Net-(VD2-K)") (class "Default")
      (node (ref "R4") (pin "1") (pinfunction "1_1") (pintype "passive"))
      (node (ref "VD2") (pin "1") (pinfunction "K_1") (pintype "passive"))
    )
    (net (code "63") (name "Net-(VD3-A)") (class "Default")
      (node (ref "VD3") (pin "2") (pinfunction "A_2") (pintype "passive"))
      (node (ref "VD7") (pin "1") (pinfunction "K_1") (pintype "passive"))
      (node (ref "XP10") (pin "1") (pinfunction "1_1") (pintype "passive"))
      (node (ref "XP4") (pin "2") (pintype "passive"))
    )
    (net (code "64") (name "Net-(VD3-K)") (class "Default")
      (node (ref "R5") (pin "1") (pinfunction "1_1") (pintype "passive"))
      (node (ref "VD3") (pin "1") (pinfunction "K_1") (pintype "passive"))
    )
    (net (code "65") (name "Net-(VD4-A)") (class "Default")
      (node (ref "VD4") (pin "2") (pinfunction "A_2") (pintype "passive"))
      (node (ref "VD8") (pin "1") (pinfunction "K_1") (pintype "passive"))
      (node (ref "XP11") (pin "1") (pinfunction "1_1") (pintype "passive"))
      (node (ref "XP5") (pin "2") (pintype "passive"))
    )
    (net (code "66") (name "Net-(VD4-K)") (class "Default")
      (node (ref "R6") (pin "1") (pinfunction "1_1") (pintype "passive"))
      (node (ref "VD4") (pin "1") (pinfunction "K_1") (pintype "passive"))
    )
    (net (code "67") (name "Net-(VD5-A)") (class "Default")
      (node (ref "R3") (pin "2") (pinfunction "2_2") (pintype "passive"))
      (node (ref "VD5") (pin "2") (pinfunction "A_2") (pintype "passive"))
      (node (ref "VT1") (pin "5") (pinfunction "5_5") (pintype "passive"))
      (node (ref "VT1") (pin "6") (pinfunction "6_6") (pintype "passive"))
      (node (ref "VT1") (pin "7") (pinfunction "7_7") (pintype "passive"))
      (node (ref "VT1") (pin "8") (pinfunction "8_8") (pintype "passive"))
      (node (ref "XP8") (pin "2") (pinfunction "2_2") (pintype "passive"))
    )
    (net (code "68") (name "Net-(VD6-A)") (class "Default")
      (node (ref "R4") (pin "2") (pinfunction "2_2") (pintype "passive"))
      (node (ref "VD6") (pin "2") (pinfunction "A_2") (pintype "passive"))
      (node (ref "VT2") (pin "5") (pinfunction "5_5") (pintype "passive"))
      (node (ref "VT2") (pin "6") (pinfunction "6_6") (pintype "passive"))
      (node (ref "VT2") (pin "7") (pinfunction "7_7") (pintype "passive"))
      (node (ref "VT2") (pin "8") (pinfunction "8_8") (pintype "passive"))
      (node (ref "XP9") (pin "2") (pinfunction "2_2") (pintype "passive"))
    )
    (net (code "69") (name "Net-(VD7-A)") (class "Default")
      (node (ref "R5") (pin "2") (pinfunction "2_2") (pintype "passive"))
      (node (ref "VD7") (pin "2") (pinfunction "A_2") (pintype "passive"))
      (node (ref "VT3") (pin "5") (pinfunction "5_5") (pintype "passive"))
      (node (ref "VT3") (pin "6") (pinfunction "6_6") (pintype "passive"))
      (node (ref "VT3") (pin "7") (pinfunction "7_7") (pintype "passive"))
      (node (ref "VT3") (pin "8") (pinfunction "8_8") (pintype "passive"))
      (node (ref "XP10") (pin "2") (pinfunction "2_2") (pintype "passive"))
    )
    (net (code "70") (name "Net-(VD8-A)") (class "Default")
      (node (ref "R6") (pin "2") (pinfunction "2_2") (pintype "passive"))
      (node (ref "VD8") (pin "2") (pinfunction "A_2") (pintype "passive"))
      (node (ref "VT4") (pin "5") (pinfunction "5_5") (pintype "passive"))
      (node (ref "VT4") (pin "6") (pinfunction "6_6") (pintype "passive"))
      (node (ref "VT4") (pin "7") (pinfunction "7_7") (pintype "passive"))
      (node (ref "VT4") (pin "8") (pinfunction "8_8") (pintype "passive"))
      (node (ref "XP11") (pin "2") (pinfunction "2_2") (pintype "passive"))
    )
    (net (code "71") (name "Net-(VD9-ka)") (class "Default")
      (node (ref "R19") (pin "1") (pinfunction "1_1") (pintype "passive"))
      (node (ref "R23") (pin "2") (pinfunction "2_2") (pintype "passive"))
      (node (ref "VD9") (pin "3") (pinfunction "ka_3") (pintype "passive"))
    )
    (net (code "72") (name "Net-(VD10-ka)") (class "Default")
      (node (ref "R20") (pin "1") (pinfunction "1_1") (pintype "passive"))
      (node (ref "R24") (pin "2") (pinfunction "2_2") (pintype "passive"))
      (node (ref "VD10") (pin "3") (pinfunction "ka_3") (pintype "passive"))
    )
    (net (code "73") (name "Net-(VD11-ka)") (class "Default")
      (node (ref "R21") (pin "1") (pinfunction "1_1") (pintype "passive"))
      (node (ref "R25") (pin "2") (pinfunction "2_2") (pintype "passive"))
      (node (ref "VD11") (pin "3") (pinfunction "ka_3") (pintype "passive"))
    )
    (net (code "74") (name "Net-(VD12-ka)") (class "Default")
      (node (ref "R22") (pin "1") (pinfunction "1_1") (pintype "passive"))
      (node (ref "R26") (pin "2") (pinfunction "2_2") (pintype "passive"))
      (node (ref "VD12") (pin "3") (pinfunction "ka_3") (pintype "passive"))
    )
    (net (code "75") (name "Net-(VD13-K)") (class "Default")
      (node (ref "R31") (pin "1") (pinfunction "1_1") (pintype "passive"))
      (node (ref "VD13") (pin "1") (pinfunction "K_1") (pintype "passive"))
    )
    (net (code "76") (name "Net-(VD14-K)") (class "Default")
      (node (ref "R32") (pin "1") (pinfunction "1_1") (pintype "passive"))
      (node (ref "VD14") (pin "1") (pinfunction "K_1") (pintype "passive"))
    )
    (net (code "77") (name "unconnected-(AD1-AD0-Pad1)") (class "Default")
      (node (ref "AD1") (pin "1") (pinfunction "AD0_1") (pintype "bidirectional+no_connect"))
    )
    (net (code "78") (name "unconnected-(AD1-AD1-Pad2)") (class "Default")
      (node (ref "AD1") (pin "2") (pinfunction "AD1_2") (pintype "bidirectional+no_connect"))
    )
    (net (code "79") (name "unconnected-(AD1-AD2-Pad3)") (class "Default")
      (node (ref "AD1") (pin "3") (pinfunction "AD2_3") (pintype "bidirectional+no_connect"))
    )
    (net (code "80") (name "unconnected-(AD1-AD3-Pad4)") (class "Default")
      (node (ref "AD1") (pin "4") (pinfunction "AD3_4") (pintype "bidirectional+no_connect"))
    )
    (net (code "81") (name "unconnected-(AD1-AD4-Pad5)") (class "Default")
      (node (ref "AD1") (pin "5") (pinfunction "AD4_5") (pintype "bidirectional+no_connect"))
    )
    (net (code "82") (name "unconnected-(AD1-AD5-Pad6)") (class "Default")
      (node (ref "AD1") (pin "6") (pinfunction "AD5_6") (pintype "bidirectional+no_connect"))
    )
    (net (code "83") (name "unconnected-(DD1-PA1{slash}OSC_IN-Pad2)") (class "Default")
      (node (ref "DD1") (pin "2") (pinfunction "PA1/OSC_IN_2") (pintype "passive"))
    )
    (net (code "84") (name "unconnected-(DD1-PA2{slash}OSC_OUT-Pad3)") (class "Default")
      (node (ref "DD1") (pin "3") (pinfunction "PA2/OSC_OUT_3") (pintype "passive"))
    )
    (net (code "85") (name "unconnected-(DD1-PA3{slash}TIM2_CH3[TIM3_CH1]-Pad9)") (class "Default")
      (node (ref "DD1") (pin "9") (pinfunction "PA3/TIM2_CH3[TIM3_CH1]_9") (pintype "passive"))
    )
    (net (code "86") (name "unconnected-(DD1-PA4-Pad10)") (class "Default")
      (node (ref "DD1") (pin "10") (pinfunction "PA4_10") (pintype "passive"))
    )
    (net (code "87") (name "unconnected-(DD1-PA5-Pad11)") (class "Default")
      (node (ref "DD1") (pin "11") (pinfunction "PA5_11") (pintype "passive"))
    )
    (net (code "88") (name "unconnected-(DD1-PC4{slash}TIM1_CH4-Pad29)") (class "Default")
      (node (ref "DD1") (pin "29") (pinfunction "PC4/TIM1_CH4_29") (pintype "passive"))
    )
    (net (code "89") (name "unconnected-(DD1-PD7{slash}TLI[TIM1_CH4]-Pad48)") (class "Default")
      (node (ref "DD1") (pin "48") (pinfunction "PD7/TLI[TIM1_CH4]_48") (pintype "passive"))
    )
    (net (code "90") (name "unconnected-(DD1-PE5{slash}SPI_NSS-Pad25)") (class "Default")
      (node (ref "DD1") (pin "25") (pinfunction "PE5/SPI_NSS_25") (pintype "passive"))
    )
    (net (code "91") (name "unconnected-(IOH1-AREF-Pad8)") (class "Default")
      (node (ref "IOH1") (pin "8") (pinfunction "AREF_8") (pintype "passive+no_connect"))
    )
    (net (code "92") (name "unconnected-(IOH1-IO8-Pad1)") (class "Default")
      (node (ref "IOH1") (pin "1") (pinfunction "IO8_1") (pintype "bidirectional+no_connect"))
    )
    (net (code "93") (name "unconnected-(IOH1-IO9-Pad2)") (class "Default")
      (node (ref "IOH1") (pin "2") (pinfunction "IO9_2") (pintype "bidirectional+no_connect"))
    )
    (net (code "94") (name "unconnected-(IOH1-IO10-Pad3)") (class "Default")
      (node (ref "IOH1") (pin "3") (pinfunction "IO10_3") (pintype "bidirectional+no_connect"))
    )
    (net (code "95") (name "unconnected-(IOL1-IO0-Pad1)") (class "Default")
      (node (ref "IOL1") (pin "1") (pinfunction "IO0_1") (pintype "bidirectional+no_connect"))
    )
    (net (code "96") (name "unconnected-(IOL1-IO1-Pad2)") (class "Default")
      (node (ref "IOL1") (pin "2") (pinfunction "IO1_2") (pintype "bidirectional+no_connect"))
    )
    (net (code "97") (name "unconnected-(IOL1-IO2-Pad3)") (class "Default")
      (node (ref "IOL1") (pin "3") (pinfunction "IO2_3") (pintype "bidirectional+no_connect"))
    )
    (net (code "98") (name "unconnected-(IOL1-IO3-Pad4)") (class "Default")
      (node (ref "IOL1") (pin "4") (pinfunction "IO3_4") (pintype "bidirectional+no_connect"))
    )
    (net (code "99") (name "unconnected-(IOL1-IO4-Pad5)") (class "Default")
      (node (ref "IOL1") (pin "5") (pinfunction "IO4_5") (pintype "bidirectional+no_connect"))
    )
    (net (code "100") (name "unconnected-(IOL1-IO5-Pad6)") (class "Default")
      (node (ref "IOL1") (pin "6") (pinfunction "IO5_6") (pintype "bidirectional+no_connect"))
    )
    (net (code "101") (name "unconnected-(IOL1-IO6-Pad7)") (class "Default")
      (node (ref "IOL1") (pin "7") (pinfunction "IO6_7") (pintype "bidirectional+no_connect"))
    )
    (net (code "102") (name "unconnected-(IOL1-IO7-Pad8)") (class "Default")
      (node (ref "IOL1") (pin "8") (pinfunction "IO7_8") (pintype "bidirectional+no_connect"))
    )
    (net (code "103") (name "unconnected-(POWER1-Pad8)") (class "Default")
      (node (ref "POWER1") (pin "8") (pintype "passive"))
    )
  )
)
